# SCH__sma__2024-12-23.net
KiCad netlist of a schematic drawn in EasyEDA
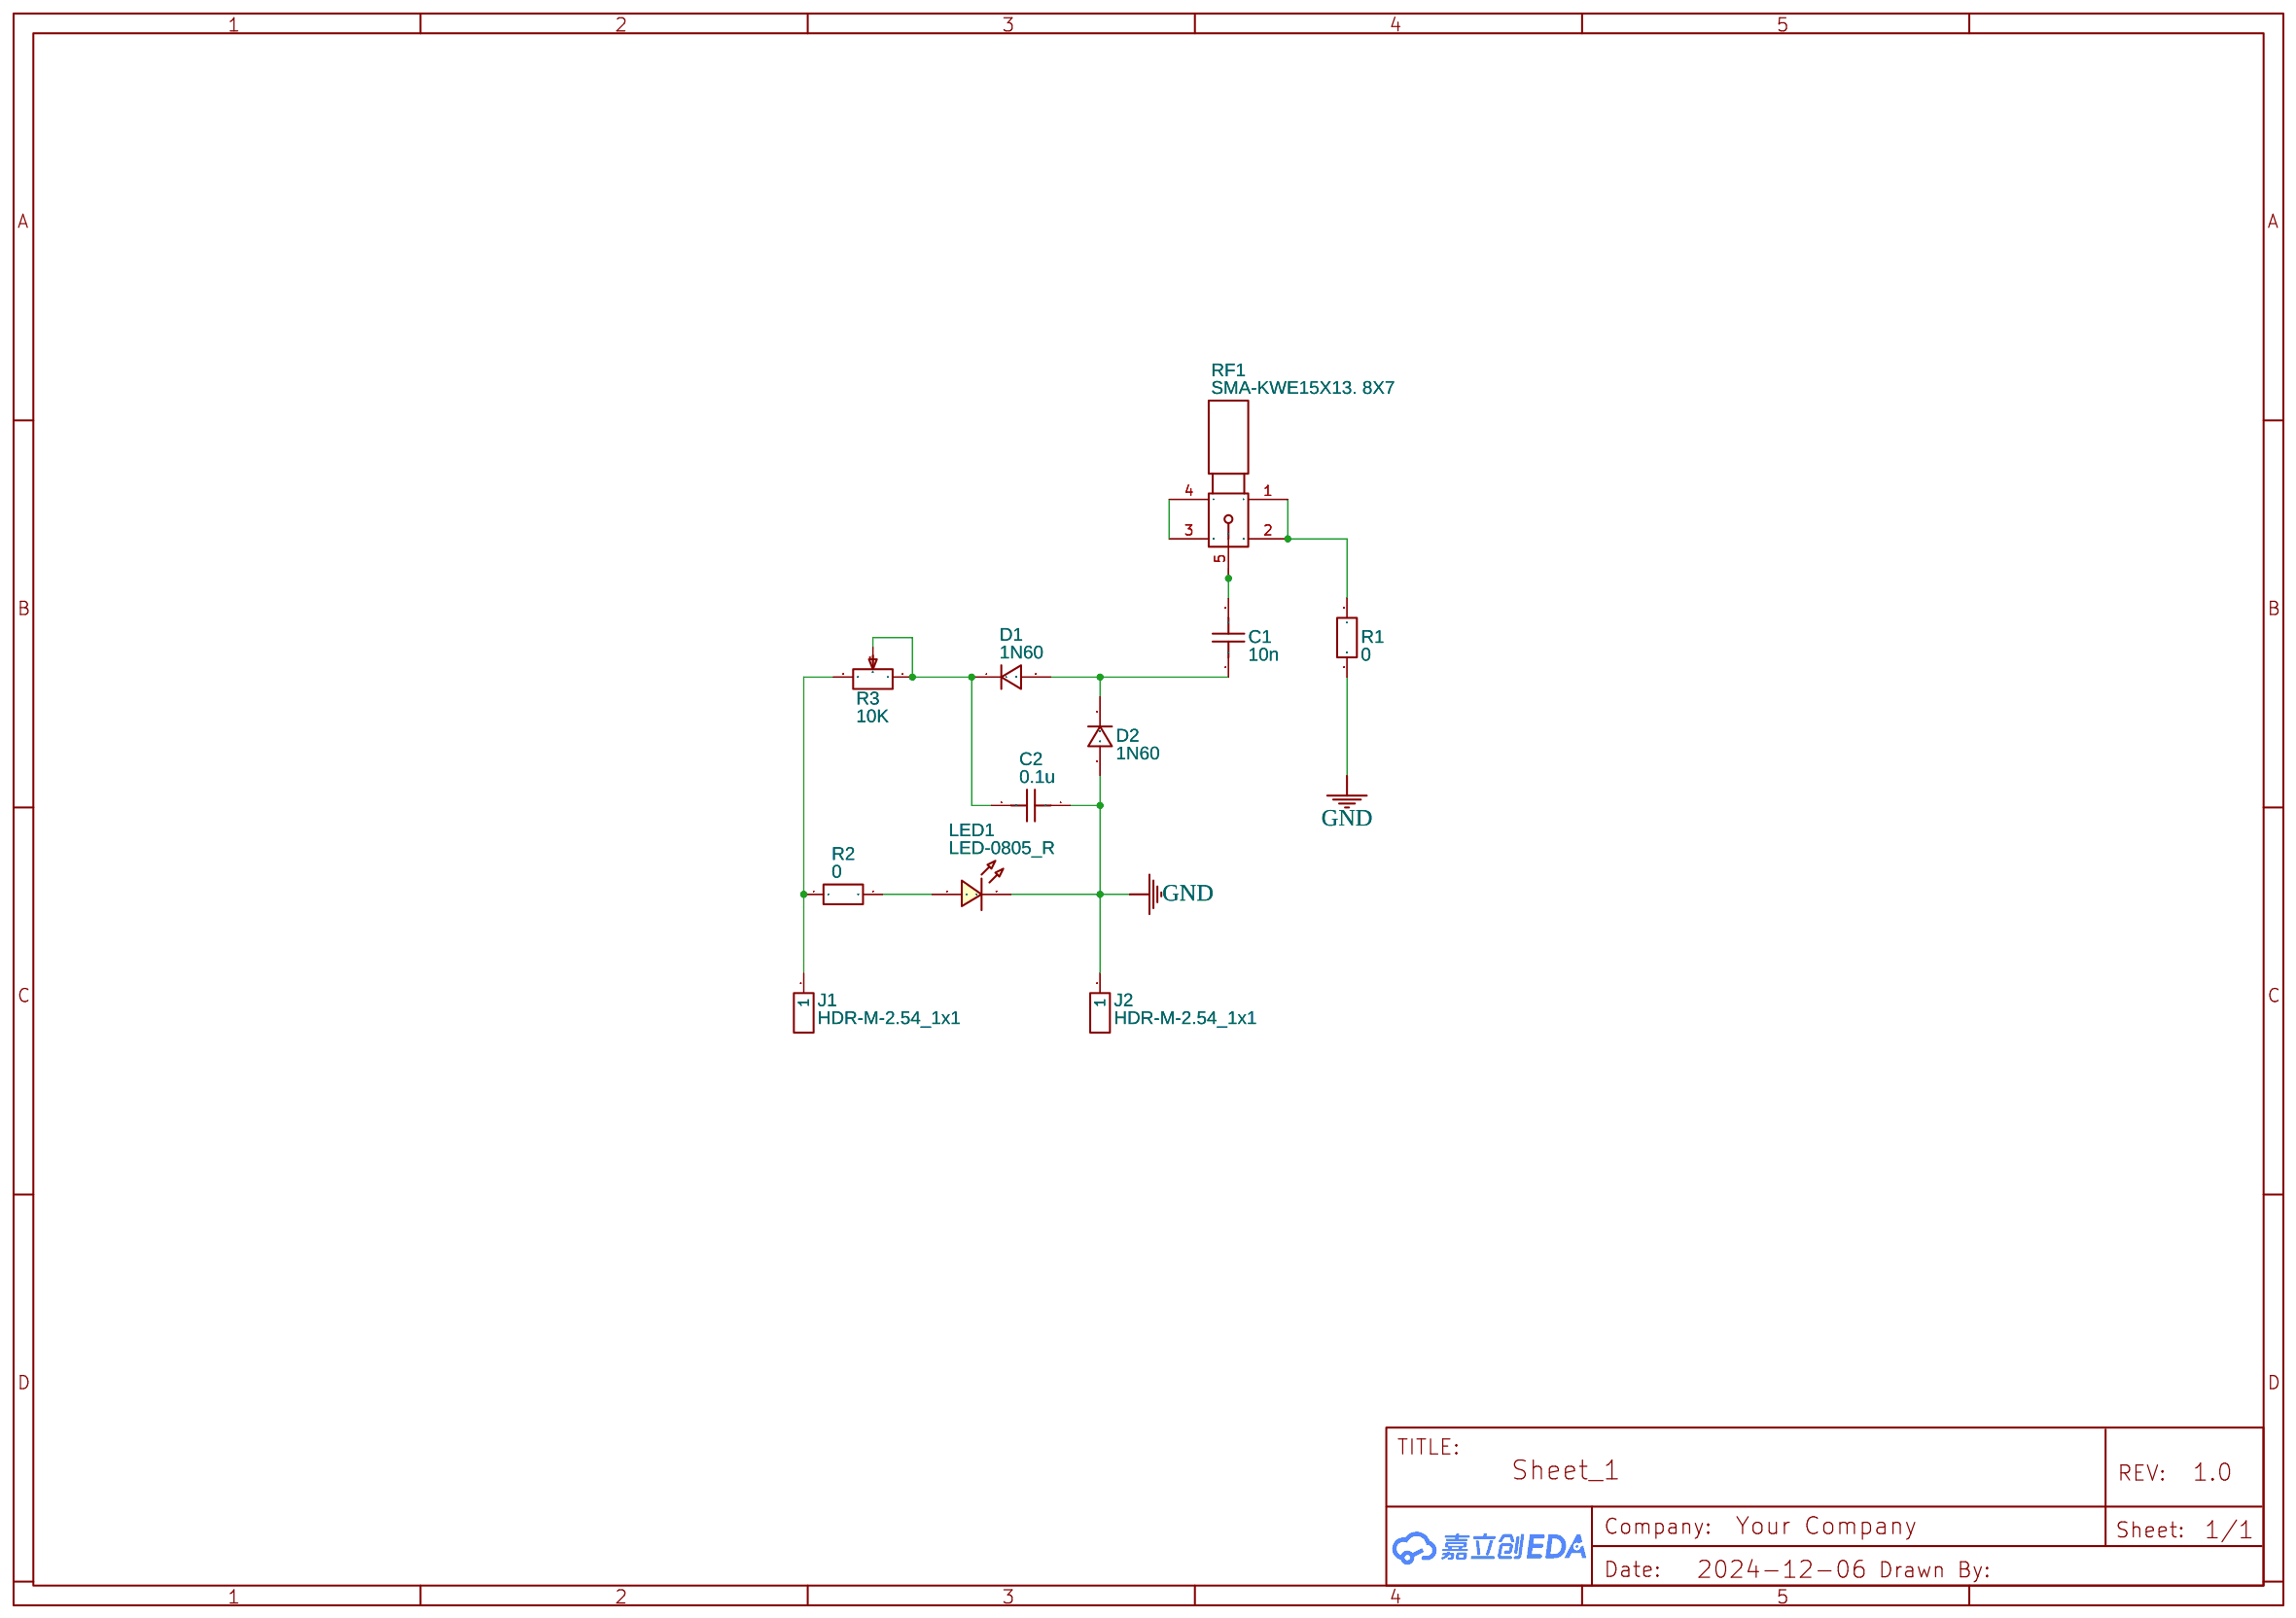
[diagram p0: schematic sheet]

(export (version "E")
  (design (tool "Eeschema 10.0.6"))
  (components
    (comp (ref "C1") (value "10n") (libsource (lib "") (part "C_0603_US_1")))
    (comp (ref "C2") (value "0.1u") (libsource (lib "") (part "C_0603_US")))
    (comp (ref "D1")
      (value "1N60")
      (fields (field (name "Manufacturer Part") "1N4148") (field (name "Manufacturer") "STMicroelectronics"))
      (libsource (lib "") (part "1N4148_1"))
    )
    (comp (ref "D2")
      (value "1N60")
      (fields (field (name "Manufacturer Part") "1N4148") (field (name "Manufacturer") "STMicroelectronics"))
      (libsource (lib "") (part "1N4148"))
    )
    (comp (ref "J1") (value "HDR-M-2.54_1x1") (libsource (lib "") (part "HDR-M-2.54_1x1")))
    (comp (ref "J2") (value "HDR-M-2.54_1x1") (libsource (lib "") (part "HDR-M-2.54_1x1")))
    (comp (ref "LED1")
      (value "LED-0805_R")
      (fields
        (field (name "Manufacturer Part") "19-217/R6C-AL1M2VY/3T")
        (field (name "Manufacturer") "EVERLIGHT(台湾亿光)")
      )
      (libsource (lib "") (part "LED-0603_R"))
    )
    (comp (ref "R1") (value "0") (libsource (lib "") (part "R_0603_EU")))
    (comp (ref "R2") (value "0") (libsource (lib "") (part "R_0603_EU_1")))
    (comp (ref "R3")
      (value "10K")
      (fields (field (name "Manufacturer Part") "WH148") (field (name "Manufacturer") "ALPS"))
      (libsource (lib "") (part "WH148"))
    )
    (comp (ref "RF1") (value "SMA-KWE15X13. 8X7") (libsource (lib "") (part "SMA-KWE15X13. 8X7")))
  )
  (nets
    (net (code "1") (name "GND") (class "Default")
      (node (ref "C2") (pin "1") (pinfunction "1_1") (pintype "unspecified"))
      (node (ref "D2") (pin "2") (pinfunction "2_2") (pintype "unspecified"))
      (node (ref "J2") (pin "1") (pinfunction "1_1") (pintype "input"))
      (node (ref "LED1") (pin "2") (pinfunction "2_2") (pintype "unspecified"))
      (node (ref "R1") (pin "1") (pinfunction "1_1") (pintype "unspecified"))
    )
    (net (code "2") (name "Net-(C1-Pad1)") (class "Default")
      (node (ref "C1") (pin "1") (pinfunction "1_1") (pintype "unspecified"))
      (node (ref "D1") (pin "2") (pinfunction "2_2") (pintype "unspecified"))
      (node (ref "D2") (pin "1") (pinfunction "1_1") (pintype "unspecified"))
    )
    (net (code "3") (name "Net-(C1-Pad2)") (class "Default")
      (node (ref "C1") (pin "2") (pinfunction "2_2") (pintype "unspecified"))
      (node (ref "RF1") (pin "5") (pinfunction "5_5") (pintype "unspecified"))
    )
    (net (code "4") (name "Net-(C2-Pad2)") (class "Default")
      (node (ref "C2") (pin "2") (pinfunction "2_2") (pintype "unspecified"))
      (node (ref "D1") (pin "1") (pinfunction "1_1") (pintype "unspecified"))
      (node (ref "R3") (pin "1") (pinfunction "1_1") (pintype "unspecified"))
      (node (ref "R3") (pin "2") (pinfunction "2_2") (pintype "unspecified"))
    )
    (net (code "5") (name "Net-(J1-Pad1)") (class "Default")
      (node (ref "J1") (pin "1") (pinfunction "1_1") (pintype "input"))
      (node (ref "R2") (pin "1") (pinfunction "1_1") (pintype "unspecified"))
      (node (ref "R3") (pin "3") (pinfunction "3_3") (pintype "unspecified"))
    )
    (net (code "6") (name "Net-(LED1-Pad1)") (class "Default")
      (node (ref "LED1") (pin "1") (pinfunction "1_1") (pintype "unspecified"))
      (node (ref "R2") (pin "2") (pinfunction "2_2") (pintype "unspecified"))
    )
    (net (code "7") (name "Net-(R1-Pad2)") (class "Default")
      (node (ref "R1") (pin "2") (pinfunction "2_2") (pintype "unspecified"))
      (node (ref "RF1") (pin "1") (pinfunction "1_1") (pintype "unspecified"))
      (node (ref "RF1") (pin "2") (pinfunction "2_2") (pintype "unspecified"))
    )
    (net (code "8") (name "Net-(RF1-Pad3)") (class "Default")
      (node (ref "RF1") (pin "3") (pinfunction "3_3") (pintype "unspecified"))
      (node (ref "RF1") (pin "4") (pinfunction "4_4") (pintype "unspecified"))
    )
  )
)
